# SIC.net
KiCad netlist of a schematic drawn in EAGLE
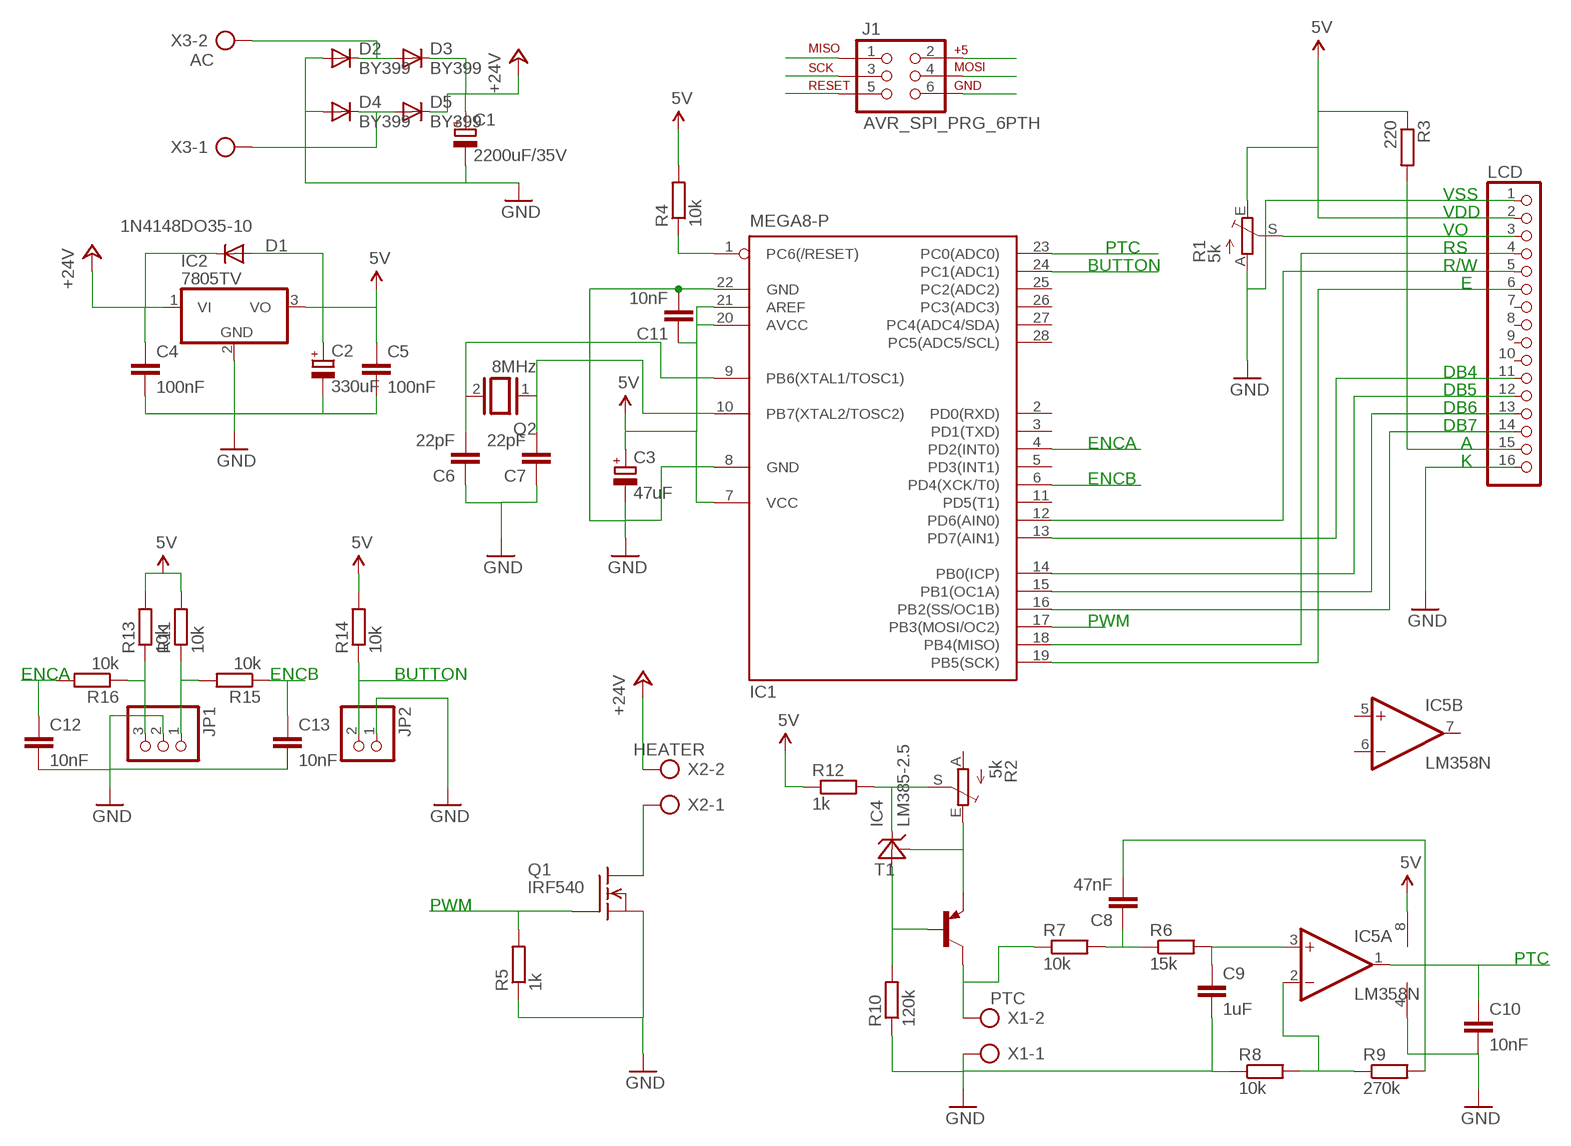
[diagram p0: schematic, sheet 1]

(export (version "E")
  (design (tool "Eeschema 10.0.6"))
  (components
    (comp (ref "C1")
      (value "2200uF/35V")
      (footprint "eagle-import:E7,5-16")
      (libsource (lib "eagle-import") (part "CPOL-EUE7.5-16"))
    )
    (comp (ref "C2")
      (value "330uF")
      (footprint "eagle-import:E3,5-8")
      (libsource (lib "eagle-import") (part "CPOL-EUE3.5-8"))
    )
    (comp (ref "C3")
      (value "47uF")
      (footprint "eagle-import:E2-5")
      (libsource (lib "eagle-import") (part "CPOL-EUE2-5"))
    )
    (comp (ref "C4")
      (value "100nF")
      (footprint "eagle-import:C050-025X075")
      (libsource (lib "eagle-import") (part "C-EU050-025X075"))
    )
    (comp (ref "C5")
      (value "100nF")
      (footprint "eagle-import:C050-025X075")
      (libsource (lib "eagle-import") (part "C-EU050-025X075"))
    )
    (comp (ref "C6")
      (value "22pF")
      (footprint "eagle-import:C050-024X044")
      (libsource (lib "eagle-import") (part "C-EU050-024X044"))
    )
    (comp (ref "C7")
      (value "22pF")
      (footprint "eagle-import:C050-024X044")
      (libsource (lib "eagle-import") (part "C-EU050-024X044"))
    )
    (comp (ref "C8")
      (value "47nF")
      (footprint "eagle-import:C050-025X075")
      (libsource (lib "eagle-import") (part "C-EU050-025X075"))
    )
    (comp (ref "C9")
      (value "1uF")
      (footprint "eagle-import:C050-030X075")
      (libsource (lib "eagle-import") (part "C-EU050-030X075"))
    )
    (comp (ref "C10")
      (value "10nF")
      (footprint "eagle-import:C050-025X075")
      (libsource (lib "eagle-import") (part "C-EU050-025X075"))
    )
    (comp (ref "C11")
      (value "10nF")
      (footprint "eagle-import:C050-025X075")
      (libsource (lib "eagle-import") (part "C-EU050-025X075"))
    )
    (comp (ref "C12")
      (value "10nF")
      (footprint "eagle-import:C050-025X075")
      (libsource (lib "eagle-import") (part "C-EU050-025X075"))
    )
    (comp (ref "C13")
      (value "10nF")
      (footprint "eagle-import:C050-025X075")
      (libsource (lib "eagle-import") (part "C-EU050-025X075"))
    )
    (comp (ref "D1")
      (value "1N4148DO35-10")
      (footprint "eagle-import:DO35-10")
      (libsource (lib "eagle-import") (part "1N4148DO35-10"))
    )
    (comp (ref "D2")
      (value "BY399")
      (footprint "eagle-import:DO201-15")
      (libsource (lib "eagle-import") (part "BY396"))
    )
    (comp (ref "D3")
      (value "BY399")
      (footprint "eagle-import:DO201-15")
      (libsource (lib "eagle-import") (part "BY396"))
    )
    (comp (ref "D4")
      (value "BY399")
      (footprint "eagle-import:DO201-15")
      (libsource (lib "eagle-import") (part "BY396"))
    )
    (comp (ref "D5")
      (value "BY399")
      (footprint "eagle-import:DO201-15")
      (libsource (lib "eagle-import") (part "BY396"))
    )
    (comp (ref "IC1")
      (value "MEGA8-P")
      (footprint "eagle-import:DIL28-3")
      (libsource (lib "eagle-import") (part "MEGA8-P"))
    )
    (comp (ref "IC2")
      (value "7805TV")
      (footprint "eagle-import:TO220V")
      (libsource (lib "eagle-import") (part "78TV05"))
    )
    (comp (ref "IC4")
      (value "LM385-2.5")
      (footprint "eagle-import:TO92-")
      (libsource (lib "eagle-import") (part "LM385-2.5"))
    )
    (comp (ref "IC5")
      (value "LM358N")
      (footprint "eagle-import:DIL08")
      (libsource (lib "eagle-import") (part "LM358N"))
    )
    (comp (ref "J1")
      (value "AVR_SPI_PRG_6PTH")
      (footprint "eagle-import:2X3")
      (libsource (lib "eagle-import") (part "AVR_SPI_PRG_6PTH"))
    )
    (comp (ref "JP1")
      (value "PINHD-1X3")
      (footprint "eagle-import:1X03")
      (libsource (lib "eagle-import") (part "PINHD-1X3"))
    )
    (comp (ref "JP2")
      (value "PINHD-1X2")
      (footprint "eagle-import:1X02")
      (libsource (lib "eagle-import") (part "PINHD-1X2"))
    )
    (comp (ref "LCD")
      (value "PINHD-1X16")
      (footprint "eagle-import:1X16")
      (libsource (lib "eagle-import") (part "PINHD-1X16"))
    )
    (comp (ref "Q1")
      (value "IRF540")
      (footprint "eagle-import:TO220")
      (libsource (lib "eagle-import") (part "IRF540"))
    )
    (comp (ref "Q2")
      (value "8MHz")
      (footprint "eagle-import:QS")
      (libsource (lib "eagle-import") (part "XTAL/S"))
    )
    (comp (ref "R1")
      (value "5k")
      (footprint "eagle-import:LI10")
      (libsource (lib "eagle-import") (part "TRIM_EU-LI10"))
    )
    (comp (ref "R2")
      (value "5k")
      (footprint "eagle-import:LI10")
      (libsource (lib "eagle-import") (part "TRIM_EU-LI10"))
    )
    (comp (ref "R3")
      (value "220")
      (footprint "eagle-import:0207_10")
      (libsource (lib "eagle-import") (part "R-EU_0207/10"))
    )
    (comp (ref "R4")
      (value "10k")
      (footprint "eagle-import:0207_10")
      (libsource (lib "eagle-import") (part "R-EU_0207/10"))
    )
    (comp (ref "R5")
      (value "1k")
      (footprint "eagle-import:0207_10")
      (libsource (lib "eagle-import") (part "R-EU_0207/10"))
    )
    (comp (ref "R6")
      (value "15k")
      (footprint "eagle-import:0207_10")
      (libsource (lib "eagle-import") (part "R-EU_0207/10"))
    )
    (comp (ref "R7")
      (value "10k")
      (footprint "eagle-import:0207_10")
      (libsource (lib "eagle-import") (part "R-EU_0207/10"))
    )
    (comp (ref "R8")
      (value "10k")
      (footprint "eagle-import:0207_10")
      (libsource (lib "eagle-import") (part "R-EU_0207/10"))
    )
    (comp (ref "R9")
      (value "270k")
      (footprint "eagle-import:0207_10")
      (libsource (lib "eagle-import") (part "R-EU_0207/10"))
    )
    (comp (ref "R10")
      (value "120k")
      (footprint "eagle-import:0207_10")
      (libsource (lib "eagle-import") (part "R-EU_0207/10"))
    )
    (comp (ref "R11")
      (value "10k")
      (footprint "eagle-import:0207_10")
      (libsource (lib "eagle-import") (part "R-EU_0207/10"))
    )
    (comp (ref "R12")
      (value "1k")
      (footprint "eagle-import:0207_10")
      (libsource (lib "eagle-import") (part "R-EU_0207/10"))
    )
    (comp (ref "R13")
      (value "10k")
      (footprint "eagle-import:0207_10")
      (libsource (lib "eagle-import") (part "R-EU_0207/10"))
    )
    (comp (ref "R14")
      (value "10k")
      (footprint "eagle-import:0207_10")
      (libsource (lib "eagle-import") (part "R-EU_0207/10"))
    )
    (comp (ref "R15")
      (value "10k")
      (footprint "eagle-import:0207_10")
      (libsource (lib "eagle-import") (part "R-EU_0207/10"))
    )
    (comp (ref "R16")
      (value "10k")
      (footprint "eagle-import:0207_10")
      (libsource (lib "eagle-import") (part "R-EU_0207/10"))
    )
    (comp (ref "T1")
      (value "BC327-16-PNP-TO92-EBC")
      (footprint "eagle-import:TO92-EBC")
      (libsource (lib "eagle-import") (part "-PNP-TO92-EBCBC327-16"))
    )
    (comp (ref "X1")
      (value "PTC")
      (footprint "eagle-import:AK300_2")
      (libsource (lib "eagle-import") (part "AK300/2"))
    )
    (comp (ref "X2")
      (value "HEATER")
      (footprint "eagle-import:AK300_2")
      (libsource (lib "eagle-import") (part "AK300/2"))
    )
    (comp (ref "X3")
      (value "AC")
      (footprint "eagle-import:AK300_2")
      (libsource (lib "eagle-import") (part "AK300/2"))
    )
  )
  (nets
    (net (code "1") (name "+24V") (class "Default")
      (node (ref "C1") (pin "+") (pinfunction "+_+") (pintype "passive"))
      (node (ref "C4") (pin "1") (pinfunction "1_1") (pintype "passive"))
      (node (ref "D1") (pin "C") (pinfunction "C_C") (pintype "passive"))
      (node (ref "D3") (pin "C") (pinfunction "C_C") (pintype "passive"))
      (node (ref "D5") (pin "C") (pinfunction "C_C") (pintype "passive"))
      (node (ref "IC2") (pin "1") (pinfunction "VI_1") (pintype "input"))
      (node (ref "X2") (pin "2") (pinfunction "KL_2") (pintype "passive"))
    )
    (net (code "2") (name "/BUTTON") (class "Default")
      (node (ref "IC1") (pin "24") (pinfunction "PC1(ADC1)_24") (pintype "bidirectional"))
      (node (ref "JP2") (pin "2") (pinfunction "2_2") (pintype "passive"))
      (node (ref "R14") (pin "1") (pinfunction "1_1") (pintype "passive"))
    )
    (net (code "3") (name "/ENCA") (class "Default")
      (node (ref "C12") (pin "1") (pinfunction "1_1") (pintype "passive"))
      (node (ref "IC1") (pin "4") (pinfunction "PD2(INT0)_4") (pintype "bidirectional"))
      (node (ref "R16") (pin "2") (pinfunction "2_2") (pintype "passive"))
    )
    (net (code "4") (name "/ENCB") (class "Default")
      (node (ref "C13") (pin "1") (pinfunction "1_1") (pintype "passive"))
      (node (ref "IC1") (pin "6") (pinfunction "PD4(XCK/T0)_6") (pintype "bidirectional"))
      (node (ref "R15") (pin "1") (pinfunction "1_1") (pintype "passive"))
    )
    (net (code "5") (name "/MISO") (class "Default")
      (node (ref "IC1") (pin "18") (pinfunction "PB4(MISO)_18") (pintype "bidirectional"))
      (node (ref "J1") (pin "1") (pinfunction "1_1") (pintype "passive"))
      (node (ref "LCD") (pin "4") (pinfunction "4_4") (pintype "passive"))
    )
    (net (code "6") (name "/MOSI_PWM") (class "Default")
      (node (ref "IC1") (pin "17") (pinfunction "PB3(MOSI/OC2)_17") (pintype "bidirectional"))
      (node (ref "J1") (pin "4") (pinfunction "4_4") (pintype "passive"))
      (node (ref "Q1") (pin "1") (pinfunction "G_1") (pintype "passive"))
      (node (ref "R5") (pin "2") (pinfunction "2_2") (pintype "passive"))
    )
    (net (code "7") (name "/PTC") (class "Default")
      (node (ref "C10") (pin "1") (pinfunction "1_1") (pintype "passive"))
      (node (ref "C8") (pin "2") (pinfunction "2_2") (pintype "passive"))
      (node (ref "IC1") (pin "23") (pinfunction "PC0(ADC0)_23") (pintype "bidirectional"))
      (node (ref "IC5") (pin "1") (pinfunction "OUT_1") (pintype "output"))
      (node (ref "R9") (pin "2") (pinfunction "2_2") (pintype "passive"))
    )
    (net (code "8") (name "/RESET") (class "Default")
      (node (ref "IC1") (pin "1") (pinfunction "PC6(/RESET)_1") (pintype "bidirectional"))
      (node (ref "J1") (pin "5") (pinfunction "5_5") (pintype "passive"))
      (node (ref "R4") (pin "1") (pinfunction "1_1") (pintype "passive"))
    )
    (net (code "9") (name "/SCK") (class "Default")
      (node (ref "IC1") (pin "19") (pinfunction "PB5(SCK)_19") (pintype "bidirectional"))
      (node (ref "J1") (pin "3") (pinfunction "3_3") (pintype "passive"))
      (node (ref "LCD") (pin "6") (pinfunction "6_6") (pintype "passive"))
    )
    (net (code "10") (name "5V") (class "Default")
      (node (ref "C11") (pin "1") (pinfunction "1_1") (pintype "passive"))
      (node (ref "C2") (pin "+") (pinfunction "+_+") (pintype "passive"))
      (node (ref "C3") (pin "+") (pinfunction "+_+") (pintype "passive"))
      (node (ref "C5") (pin "1") (pinfunction "1_1") (pintype "passive"))
      (node (ref "D1") (pin "A") (pinfunction "A_A") (pintype "passive"))
      (node (ref "IC1") (pin "20") (pinfunction "AVCC_20") (pintype "power_in"))
      (node (ref "IC1") (pin "21") (pinfunction "AREF_21") (pintype "passive"))
      (node (ref "IC1") (pin "7") (pinfunction "VCC_7") (pintype "power_in"))
      (node (ref "IC2") (pin "3") (pinfunction "VO_3") (pintype "passive"))
      (node (ref "IC5") (pin "8") (pinfunction "V+_8") (pintype "power_in"))
      (node (ref "J1") (pin "2") (pinfunction "2_2") (pintype "passive"))
      (node (ref "LCD") (pin "2") (pinfunction "2_2") (pintype "passive"))
      (node (ref "R1") (pin "E") (pinfunction "E_E") (pintype "passive"))
      (node (ref "R11") (pin "2") (pinfunction "2_2") (pintype "passive"))
      (node (ref "R12") (pin "1") (pinfunction "1_1") (pintype "passive"))
      (node (ref "R13") (pin "2") (pinfunction "2_2") (pintype "passive"))
      (node (ref "R14") (pin "2") (pinfunction "2_2") (pintype "passive"))
      (node (ref "R3") (pin "1") (pinfunction "1_1") (pintype "passive"))
      (node (ref "R4") (pin "2") (pinfunction "2_2") (pintype "passive"))
    )
    (net (code "11") (name "GND") (class "Default")
      (node (ref "C1") (pin "-") (pinfunction "-_-") (pintype "passive"))
      (node (ref "C10") (pin "2") (pinfunction "2_2") (pintype "passive"))
      (node (ref "C11") (pin "2") (pinfunction "2_2") (pintype "passive"))
      (node (ref "C12") (pin "2") (pinfunction "2_2") (pintype "passive"))
      (node (ref "C13") (pin "2") (pinfunction "2_2") (pintype "passive"))
      (node (ref "C2") (pin "-") (pinfunction "-_-") (pintype "passive"))
      (node (ref "C3") (pin "-") (pinfunction "-_-") (pintype "passive"))
      (node (ref "C4") (pin "2") (pinfunction "2_2") (pintype "passive"))
      (node (ref "C5") (pin "2") (pinfunction "2_2") (pintype "passive"))
      (node (ref "C6") (pin "1") (pinfunction "1_1") (pintype "passive"))
      (node (ref "C7") (pin "1") (pinfunction "1_1") (pintype "passive"))
      (node (ref "C9") (pin "2") (pinfunction "2_2") (pintype "passive"))
      (node (ref "D2") (pin "A") (pinfunction "A_A") (pintype "passive"))
      (node (ref "D4") (pin "A") (pinfunction "A_A") (pintype "passive"))
      (node (ref "IC1") (pin "22") (pinfunction "GND_22") (pintype "power_in"))
      (node (ref "IC1") (pin "8") (pinfunction "GND_8") (pintype "power_in"))
      (node (ref "IC2") (pin "2") (pinfunction "GND_2") (pintype "passive"))
      (node (ref "IC5") (pin "4") (pinfunction "V-_4") (pintype "power_in"))
      (node (ref "J1") (pin "6") (pinfunction "6_6") (pintype "passive"))
      (node (ref "JP1") (pin "2") (pinfunction "2_2") (pintype "passive"))
      (node (ref "JP2") (pin "1") (pinfunction "1_1") (pintype "passive"))
      (node (ref "LCD") (pin "1") (pinfunction "1_1") (pintype "passive"))
      (node (ref "LCD") (pin "16") (pinfunction "16_16") (pintype "passive"))
      (node (ref "Q1") (pin "3") (pinfunction "S_3") (pintype "passive"))
      (node (ref "R1") (pin "A") (pinfunction "A_A") (pintype "passive"))
      (node (ref "R10") (pin "1") (pinfunction "1_1") (pintype "passive"))
      (node (ref "R5") (pin "1") (pinfunction "1_1") (pintype "passive"))
      (node (ref "R8") (pin "1") (pinfunction "1_1") (pintype "passive"))
      (node (ref "X1") (pin "1") (pinfunction "KL_1") (pintype "passive"))
    )
    (net (code "12") (name "Net-(C8-Pad1)") (class "Default")
      (node (ref "C8") (pin "1") (pinfunction "1_1") (pintype "passive"))
      (node (ref "R6") (pin "1") (pinfunction "1_1") (pintype "passive"))
      (node (ref "R7") (pin "2") (pinfunction "2_2") (pintype "passive"))
    )
    (net (code "13") (name "Net-(IC1-PB0(ICP))") (class "Default")
      (node (ref "IC1") (pin "14") (pinfunction "PB0(ICP)_14") (pintype "bidirectional"))
      (node (ref "LCD") (pin "12") (pinfunction "12_12") (pintype "passive"))
    )
    (net (code "14") (name "Net-(IC1-PB1(OC1A))") (class "Default")
      (node (ref "IC1") (pin "15") (pinfunction "PB1(OC1A)_15") (pintype "bidirectional"))
      (node (ref "LCD") (pin "13") (pinfunction "13_13") (pintype "passive"))
    )
    (net (code "15") (name "Net-(IC1-PB2(SS{slash}OC1B))") (class "Default")
      (node (ref "IC1") (pin "16") (pinfunction "PB2(SS/OC1B)_16") (pintype "bidirectional"))
      (node (ref "LCD") (pin "14") (pinfunction "14_14") (pintype "passive"))
    )
    (net (code "16") (name "Net-(IC1-PB6(XTAL1{slash}TOSC1))") (class "Default")
      (node (ref "C6") (pin "2") (pinfunction "2_2") (pintype "passive"))
      (node (ref "IC1") (pin "9") (pinfunction "PB6(XTAL1/TOSC1)_9") (pintype "bidirectional"))
      (node (ref "Q2") (pin "2") (pinfunction "2_2") (pintype "passive"))
    )
    (net (code "17") (name "Net-(IC1-PB7(XTAL2{slash}TOSC2))") (class "Default")
      (node (ref "C7") (pin "2") (pinfunction "2_2") (pintype "passive"))
      (node (ref "IC1") (pin "10") (pinfunction "PB7(XTAL2/TOSC2)_10") (pintype "bidirectional"))
      (node (ref "Q2") (pin "1") (pinfunction "1_1") (pintype "passive"))
    )
    (net (code "18") (name "Net-(IC1-PD6(AIN0))") (class "Default")
      (node (ref "IC1") (pin "12") (pinfunction "PD6(AIN0)_12") (pintype "bidirectional"))
      (node (ref "LCD") (pin "5") (pinfunction "5_5") (pintype "passive"))
    )
    (net (code "19") (name "Net-(IC1-PD7(AIN1))") (class "Default")
      (node (ref "IC1") (pin "13") (pinfunction "PD7(AIN1)_13") (pintype "bidirectional"))
      (node (ref "LCD") (pin "11") (pinfunction "11_11") (pintype "passive"))
    )
    (net (code "20") (name "Net-(IC4-A)") (class "Default")
      (node (ref "IC4") (pin "1") (pinfunction "A_1") (pintype "passive"))
      (node (ref "R10") (pin "2") (pinfunction "2_2") (pintype "passive"))
      (node (ref "T1") (pin "B") (pinfunction "B_B") (pintype "passive"))
    )
    (net (code "21") (name "Net-(IC4-C)") (class "Default")
      (node (ref "IC4") (pin "2") (pinfunction "C_2") (pintype "passive"))
      (node (ref "R12") (pin "2") (pinfunction "2_2") (pintype "passive"))
      (node (ref "R2") (pin "S") (pinfunction "S_S") (pintype "passive"))
    )
    (net (code "22") (name "Net-(IC4-FB)") (class "Default")
      (node (ref "IC4") (pin "3") (pinfunction "FB_3") (pintype "passive"))
      (node (ref "R2") (pin "E") (pinfunction "E_E") (pintype "passive"))
      (node (ref "T1") (pin "E") (pinfunction "E_E") (pintype "passive"))
    )
    (net (code "23") (name "Net-(IC5A-+IN)") (class "Default")
      (node (ref "C9") (pin "1") (pinfunction "1_1") (pintype "passive"))
      (node (ref "IC5") (pin "3") (pinfunction "+IN_3") (pintype "input"))
      (node (ref "R6") (pin "2") (pinfunction "2_2") (pintype "passive"))
    )
    (net (code "24") (name "Net-(IC5A--IN)") (class "Default")
      (node (ref "IC5") (pin "2") (pinfunction "-IN_2") (pintype "input"))
      (node (ref "R8") (pin "2") (pinfunction "2_2") (pintype "passive"))
      (node (ref "R9") (pin "1") (pinfunction "1_1") (pintype "passive"))
    )
    (net (code "25") (name "Net-(JP1-Pad1)") (class "Default")
      (node (ref "JP1") (pin "1") (pinfunction "1_1") (pintype "passive"))
      (node (ref "R11") (pin "1") (pinfunction "1_1") (pintype "passive"))
      (node (ref "R15") (pin "2") (pinfunction "2_2") (pintype "passive"))
    )
    (net (code "26") (name "Net-(JP1-Pad3)") (class "Default")
      (node (ref "JP1") (pin "3") (pinfunction "3_3") (pintype "passive"))
      (node (ref "R13") (pin "1") (pinfunction "1_1") (pintype "passive"))
      (node (ref "R16") (pin "1") (pinfunction "1_1") (pintype "passive"))
    )
    (net (code "27") (name "Net-(LCD-Pad3)") (class "Default")
      (node (ref "LCD") (pin "3") (pinfunction "3_3") (pintype "passive"))
      (node (ref "R1") (pin "S") (pinfunction "S_S") (pintype "passive"))
    )
    (net (code "28") (name "Net-(LCD-Pad15)") (class "Default")
      (node (ref "LCD") (pin "15") (pinfunction "15_15") (pintype "passive"))
      (node (ref "R3") (pin "2") (pinfunction "2_2") (pintype "passive"))
    )
    (net (code "29") (name "Net-(Q1-D)") (class "Default")
      (node (ref "Q1") (pin "2") (pinfunction "D_2") (pintype "passive"))
      (node (ref "X2") (pin "1") (pinfunction "KL_1") (pintype "passive"))
    )
    (net (code "30") (name "Net-(X1B-KL)") (class "Default")
      (node (ref "R7") (pin "1") (pinfunction "1_1") (pintype "passive"))
      (node (ref "T1") (pin "C") (pinfunction "C_C") (pintype "passive"))
      (node (ref "X1") (pin "2") (pinfunction "KL_2") (pintype "passive"))
    )
    (net (code "31") (name "Net-(X3A-KL)") (class "Default")
      (node (ref "D4") (pin "C") (pinfunction "C_C") (pintype "passive"))
      (node (ref "D5") (pin "A") (pinfunction "A_A") (pintype "passive"))
      (node (ref "X3") (pin "1") (pinfunction "KL_1") (pintype "passive"))
    )
    (net (code "32") (name "Net-(X3B-KL)") (class "Default")
      (node (ref "D2") (pin "C") (pinfunction "C_C") (pintype "passive"))
      (node (ref "D3") (pin "A") (pinfunction "A_A") (pintype "passive"))
      (node (ref "X3") (pin "2") (pinfunction "KL_2") (pintype "passive"))
    )
    (net (code "33") (name "unconnected-(IC1-PC2(ADC2)-Pad25)") (class "Default")
      (node (ref "IC1") (pin "25") (pinfunction "PC2(ADC2)_25") (pintype "bidirectional"))
    )
    (net (code "34") (name "unconnected-(IC1-PC3(ADC3)-Pad26)") (class "Default")
      (node (ref "IC1") (pin "26") (pinfunction "PC3(ADC3)_26") (pintype "bidirectional"))
    )
    (net (code "35") (name "unconnected-(IC1-PC4(ADC4{slash}SDA)-Pad27)") (class "Default")
      (node (ref "IC1") (pin "27") (pinfunction "PC4(ADC4/SDA)_27") (pintype "bidirectional"))
    )
    (net (code "36") (name "unconnected-(IC1-PC5(ADC5{slash}SCL)-Pad28)") (class "Default")
      (node (ref "IC1") (pin "28") (pinfunction "PC5(ADC5/SCL)_28") (pintype "bidirectional"))
    )
    (net (code "37") (name "unconnected-(IC1-PD0(RXD)-Pad2)") (class "Default")
      (node (ref "IC1") (pin "2") (pinfunction "PD0(RXD)_2") (pintype "bidirectional"))
    )
    (net (code "38") (name "unconnected-(IC1-PD1(TXD)-Pad3)") (class "Default")
      (node (ref "IC1") (pin "3") (pinfunction "PD1(TXD)_3") (pintype "bidirectional"))
    )
    (net (code "39") (name "unconnected-(IC1-PD3(INT1)-Pad5)") (class "Default")
      (node (ref "IC1") (pin "5") (pinfunction "PD3(INT1)_5") (pintype "bidirectional"))
    )
    (net (code "40") (name "unconnected-(IC1-PD5(T1)-Pad11)") (class "Default")
      (node (ref "IC1") (pin "11") (pinfunction "PD5(T1)_11") (pintype "bidirectional"))
    )
    (net (code "41") (name "unconnected-(IC5B-+IN-Pad5)") (class "Default")
      (node (ref "IC5") (pin "5") (pinfunction "+IN_5") (pintype "input"))
    )
    (net (code "42") (name "unconnected-(IC5B--IN-Pad6)") (class "Default")
      (node (ref "IC5") (pin "6") (pinfunction "-IN_6") (pintype "input"))
    )
    (net (code "43") (name "unconnected-(IC5B-OUT-Pad7)") (class "Default")
      (node (ref "IC5") (pin "7") (pinfunction "OUT_7") (pintype "output"))
    )
    (net (code "44") (name "unconnected-(LCD-Pad7)") (class "Default")
      (node (ref "LCD") (pin "7") (pinfunction "7_7") (pintype "passive"))
    )
    (net (code "45") (name "unconnected-(LCD-Pad8)") (class "Default")
      (node (ref "LCD") (pin "8") (pinfunction "8_8") (pintype "passive"))
    )
    (net (code "46") (name "unconnected-(LCD-Pad9)") (class "Default")
      (node (ref "LCD") (pin "9") (pinfunction "9_9") (pintype "passive"))
    )
    (net (code "47") (name "unconnected-(LCD-Pad10)") (class "Default")
      (node (ref "LCD") (pin "10") (pinfunction "10_10") (pintype "passive"))
    )
    (net (code "48") (name "unconnected-(R2-PadA)") (class "Default")
      (node (ref "R2") (pin "A") (pinfunction "A_A") (pintype "passive"))
    )
  )
)
